# Adafruit_microsd.net
KiCad netlist of a schematic drawn in EAGLE
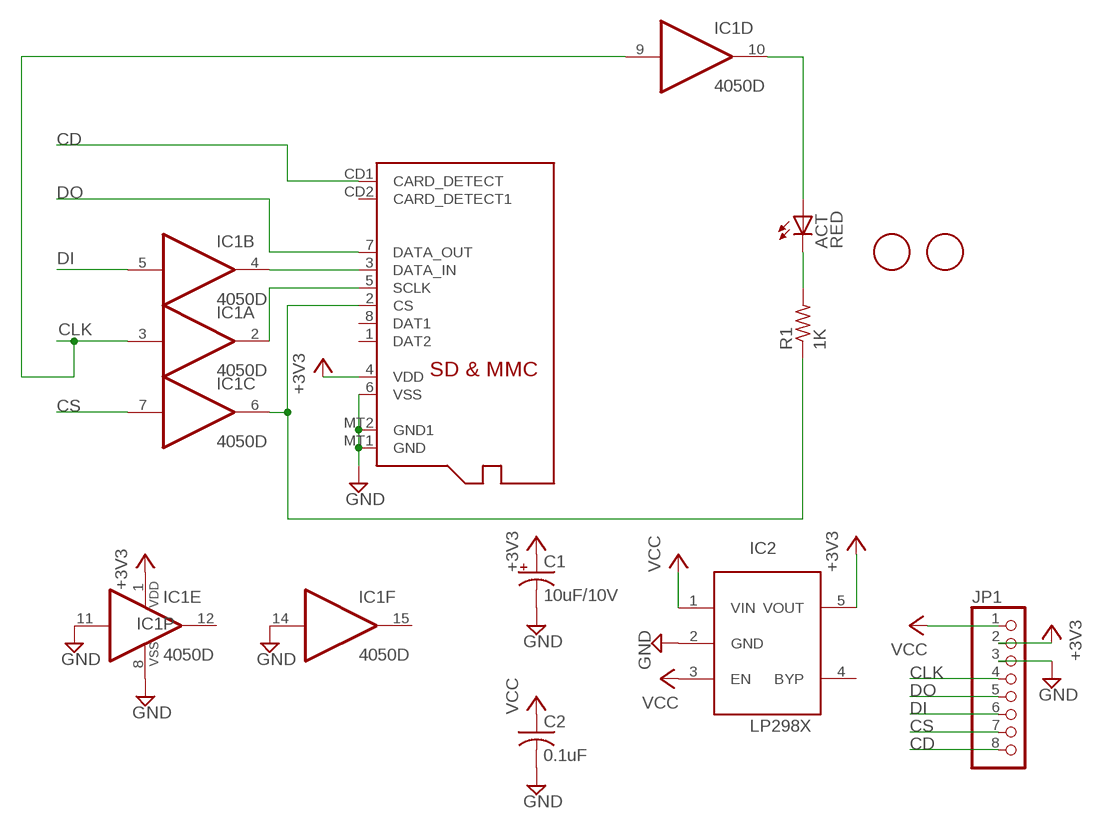
[diagram p0: schematic, sheet 1]

(export (version "E")
  (design (tool "Eeschema 10.0.6"))
  (components
    (comp (ref "ACT")
      (value "RED")
      (footprint "eagle-import:CHIP-LED0805")
      (libsource (lib "eagle-import") (part "LEDCHIP-LED0805"))
    )
    (comp (ref "C1")
      (value "10uF/10V")
      (footprint "eagle-import:A_3216-18R")
      (libsource (lib "eagle-import") (part "CPOL-USA/3216-18R"))
    )
    (comp (ref "C2")
      (value "0.1uF")
      (footprint "eagle-import:C0805K")
      (libsource (lib "eagle-import") (part "C-USC0805K"))
    )
    (comp (ref "IC1")
      (value "4050D")
      (footprint "eagle-import:SO16")
      (libsource (lib "eagle-import") (part "4050D"))
    )
    (comp (ref "IC2")
      (value "LP298XS")
      (footprint "eagle-import:SOT23-5L")
      (libsource (lib "eagle-import") (part "LP298XS"))
    )
    (comp (ref "JP1")
      (value "PINHD-1X8BIG")
      (footprint "eagle-import:1X08-BIG")
      (libsource (lib "eagle-import") (part "PINHD-1X8BIG"))
    )
    (comp (ref "R1")
      (value "1K")
      (footprint "eagle-import:R0805")
      (libsource (lib "eagle-import") (part "R-US_R0805"))
    )
    (comp (ref "U$1")
      (value "FIDUCIAL")
      (footprint "eagle-import:FIDUCIAL_1MM")
      (libsource (lib "eagle-import") (part "FIDUCIAL"))
    )
    (comp (ref "U$2")
      (value "FIDUCIAL")
      (footprint "eagle-import:FIDUCIAL_1MM")
      (libsource (lib "eagle-import") (part "FIDUCIAL"))
    )
    (comp (ref "X1")
      (value "MICROSD")
      (footprint "eagle-import:MICROSD")
      (libsource (lib "eagle-import") (part "MICROSD"))
    )
  )
  (nets
    (net (code "1") (name "+3V3") (class "Default")
      (node (ref "C1") (pin "+") (pinfunction "+_+") (pintype "passive"))
      (node (ref "IC1") (pin "1") (pinfunction "VDD_1") (pintype "power_in"))
      (node (ref "IC2") (pin "5") (pinfunction "VOUT_5") (pintype "bidirectional"))
      (node (ref "JP1") (pin "2") (pinfunction "2_2") (pintype "passive"))
      (node (ref "X1") (pin "4") (pinfunction "VDD_4") (pintype "power_in"))
    )
    (net (code "2") (name "/CD") (class "Default")
      (node (ref "JP1") (pin "8") (pinfunction "8_8") (pintype "passive"))
      (node (ref "X1") (pin "CD1") (pinfunction "CARD_DETECT_CD1") (pintype "passive"))
    )
    (net (code "3") (name "/CLK") (class "Default")
      (node (ref "IC1") (pin "3") (pinfunction "I_3") (pintype "input"))
      (node (ref "IC1") (pin "9") (pinfunction "I_9") (pintype "input"))
      (node (ref "JP1") (pin "4") (pinfunction "4_4") (pintype "passive"))
    )
    (net (code "4") (name "/CS") (class "Default")
      (node (ref "IC1") (pin "7") (pinfunction "I_7") (pintype "input"))
      (node (ref "JP1") (pin "7") (pinfunction "7_7") (pintype "passive"))
    )
    (net (code "5") (name "/DI") (class "Default")
      (node (ref "IC1") (pin "5") (pinfunction "I_5") (pintype "input"))
      (node (ref "JP1") (pin "6") (pinfunction "6_6") (pintype "passive"))
    )
    (net (code "6") (name "/DO") (class "Default")
      (node (ref "JP1") (pin "5") (pinfunction "5_5") (pintype "passive"))
      (node (ref "X1") (pin "7") (pinfunction "DATA_OUT_7") (pintype "output"))
    )
    (net (code "7") (name "GND") (class "Default")
      (node (ref "C1") (pin "-") (pinfunction "-_-") (pintype "passive"))
      (node (ref "C2") (pin "2") (pinfunction "2_2") (pintype "passive"))
      (node (ref "IC1") (pin "11") (pinfunction "I_11") (pintype "input"))
      (node (ref "IC1") (pin "14") (pinfunction "I_14") (pintype "input"))
      (node (ref "IC1") (pin "8") (pinfunction "VSS_8") (pintype "power_in"))
      (node (ref "IC2") (pin "2") (pinfunction "GND_2") (pintype "bidirectional"))
      (node (ref "JP1") (pin "3") (pinfunction "3_3") (pintype "passive"))
      (node (ref "X1") (pin "6") (pinfunction "VSS_6") (pintype "power_in"))
      (node (ref "X1") (pin "MT1") (pinfunction "GND_MT1") (pintype "power_in"))
      (node (ref "X1") (pin "MT2") (pinfunction "GND1_MT2") (pintype "power_in"))
    )
    (net (code "8") (name "Net-(ACT-PadC)") (class "Default")
      (node (ref "ACT") (pin "C") (pinfunction "C_C") (pintype "passive"))
      (node (ref "R1") (pin "2") (pinfunction "2_2") (pintype "passive"))
    )
    (net (code "9") (name "Net-(IC1A-O)") (class "Default")
      (node (ref "IC1") (pin "2") (pinfunction "O_2") (pintype "output"))
      (node (ref "X1") (pin "5") (pinfunction "SCLK_5") (pintype "input"))
    )
    (net (code "10") (name "Net-(IC1B-O)") (class "Default")
      (node (ref "IC1") (pin "4") (pinfunction "O_4") (pintype "output"))
      (node (ref "X1") (pin "3") (pinfunction "DATA_IN_3") (pintype "input"))
    )
    (net (code "11") (name "Net-(IC1C-O)") (class "Default")
      (node (ref "IC1") (pin "6") (pinfunction "O_6") (pintype "output"))
      (node (ref "R1") (pin "1") (pinfunction "1_1") (pintype "passive"))
      (node (ref "X1") (pin "2") (pinfunction "CS_2") (pintype "input"))
    )
    (net (code "12") (name "Net-(IC1D-O)") (class "Default")
      (node (ref "ACT") (pin "A") (pinfunction "A_A") (pintype "passive"))
      (node (ref "IC1") (pin "10") (pinfunction "O_10") (pintype "output"))
    )
    (net (code "13") (name "VCC") (class "Default")
      (node (ref "C2") (pin "1") (pinfunction "1_1") (pintype "passive"))
      (node (ref "IC2") (pin "1") (pinfunction "VIN_1") (pintype "bidirectional"))
      (node (ref "IC2") (pin "3") (pinfunction "EN_3") (pintype "bidirectional"))
      (node (ref "JP1") (pin "1") (pinfunction "1_1") (pintype "passive"))
    )
    (net (code "14") (name "unconnected-(IC1E-O-Pad12)") (class "Default")
      (node (ref "IC1") (pin "12") (pinfunction "O_12") (pintype "output"))
    )
    (net (code "15") (name "unconnected-(IC1F-O-Pad15)") (class "Default")
      (node (ref "IC1") (pin "15") (pinfunction "O_15") (pintype "output"))
    )
    (net (code "16") (name "unconnected-(IC2-BYP-Pad4)") (class "Default")
      (node (ref "IC2") (pin "4") (pinfunction "BYP_4") (pintype "bidirectional"))
    )
    (net (code "17") (name "unconnected-(X1-CARD_DETECT1-PadCD2)") (class "Default")
      (node (ref "X1") (pin "CD2") (pinfunction "CARD_DETECT1_CD2") (pintype "passive"))
    )
    (net (code "18") (name "unconnected-(X1-DAT1-Pad8)") (class "Default")
      (node (ref "X1") (pin "8") (pinfunction "DAT1_8") (pintype "bidirectional"))
    )
    (net (code "19") (name "unconnected-(X1-DAT2-Pad1)") (class "Default")
      (node (ref "X1") (pin "1") (pinfunction "DAT2_1") (pintype "bidirectional"))
    )
  )
)
